# Communication_Display.net
KiCad netlist of a schematic drawn in Altium Designer
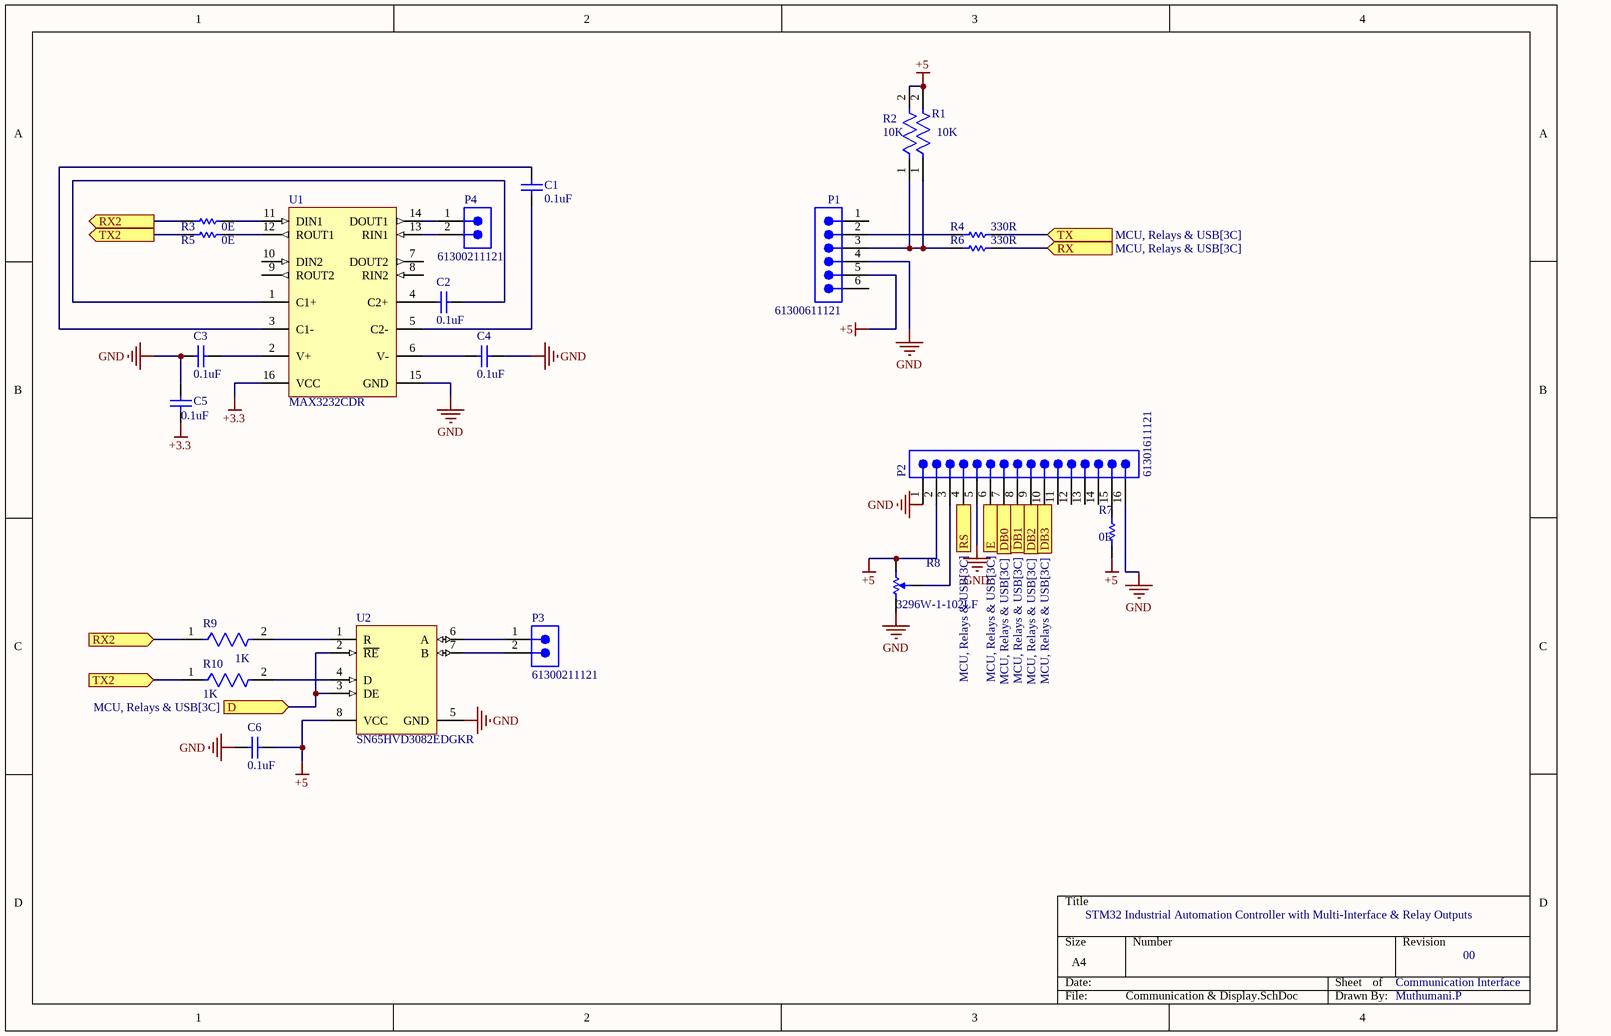
[diagram p0: Communication & Display.SchDoc]

(export (version "E")
  (design (tool "Eeschema 10.0.6"))
  (components
    (comp (ref "C1")
      (value "0.1uF")
      (footprint "CAPC1608X90X35ML10T15")
      (description "Chip Capacitor, 0.1 uF, +/- 10%, 50 V, -55 to 125 degC, 0603 (1608 Metric), RoHS, Tape and Reel")
      (fields (field (name "TOLERANCE") "10%") (field (name "VOLTAGE") "50V"))
      (libsource (lib "Altium Content Vault") (part "CAP-NP-2"))
    )
    (comp (ref "C2")
      (value "0.1uF")
      (footprint "CAPC1608X90X35ML10T15")
      (description "Chip Capacitor, 0.1 uF, +/- 10%, 50 V, -55 to 125 degC, 0603 (1608 Metric), RoHS, Tape and Reel")
      (fields (field (name "TOLERANCE") "10%") (field (name "VOLTAGE") "50V"))
      (libsource (lib "Altium Content Vault") (part "CAP-NP-2"))
    )
    (comp (ref "C3")
      (value "0.1uF")
      (footprint "CAPC1608X90X35ML10T15")
      (description "Chip Capacitor, 0.1 uF, +/- 10%, 50 V, -55 to 125 degC, 0603 (1608 Metric), RoHS, Tape and Reel")
      (fields (field (name "TOLERANCE") "10%") (field (name "VOLTAGE") "50V"))
      (libsource (lib "Altium Content Vault") (part "CAP-NP-2"))
    )
    (comp (ref "C4")
      (value "0.1uF")
      (footprint "CAPC1608X90X35ML10T15")
      (description "Chip Capacitor, 0.1 uF, +/- 10%, 50 V, -55 to 125 degC, 0603 (1608 Metric), RoHS, Tape and Reel")
      (fields (field (name "TOLERANCE") "10%") (field (name "VOLTAGE") "50V"))
      (libsource (lib "Altium Content Vault") (part "CAP-NP-2"))
    )
    (comp (ref "C5")
      (value "0.1uF")
      (footprint "CAPC1608X90X35ML10T15")
      (description "Chip Capacitor, 0.1 uF, +/- 10%, 50 V, -55 to 125 degC, 0603 (1608 Metric), RoHS, Tape and Reel")
      (fields (field (name "TOLERANCE") "10%") (field (name "VOLTAGE") "50V"))
      (libsource (lib "Altium Content Vault") (part "CAP-NP-2"))
    )
    (comp (ref "C6")
      (value "0.1uF")
      (footprint "CAPC1608X90X35ML10T15")
      (description "Chip Capacitor, 0.1 uF, +/- 10%, 50 V, -55 to 125 degC, 0603 (1608 Metric), RoHS, Tape and Reel")
      (fields (field (name "TOLERANCE") "10%") (field (name "VOLTAGE") "50V"))
      (libsource (lib "Altium Content Vault") (part "CAP-NP-2"))
    )
    (comp (ref "P1")
      (value "61300611121")
      (footprint "61300611121")
      (description "THT Vertical Pin Header WR-PHD, Pitch 2.54 mm, Single Row, 6 pins")
      (libsource (lib "Altium Content Vault") (part "Header_Male_1R_06P"))
    )
    (comp (ref "P2")
      (value "61301611121")
      (footprint "61301611121")
      (description "THT Vertical Pin Header WR-PHD, Pitch 2.54 mm, Single Row, 16 pins")
      (libsource (lib "Altium Content Vault") (part "Header_Male_1R_16P"))
    )
    (comp (ref "P3")
      (value "61300211121")
      (footprint "61300211121")
      (description "THT Vertical Pin Header WR-PHD, Pitch 2.54 mm, Single Row, 2 pins")
      (libsource (lib "Altium Content Vault") (part "Header_Male_1R_02P"))
    )
    (comp (ref "P4")
      (value "61300211121")
      (footprint "61300211121")
      (description "THT Vertical Pin Header WR-PHD, Pitch 2.54 mm, Single Row, 2 pins")
      (libsource (lib "Altium Content Vault") (part "Header_Male_1R_02P"))
    )
    (comp (ref "R1")
      (value "10K")
      (footprint "FP-RC0603-0_55-IPC_C")
      (description "RES 10K OHM 1% 1/10W 0603")
      (fields (field (name "TOLERANCE") "1%"))
      (libsource (lib "Altium Content Vault") (part "1029c3af85768c4190bb7ad29bc67b5"))
    )
    (comp (ref "R2")
      (value "10K")
      (footprint "FP-RC0603-0_55-IPC_C")
      (description "RES 10K OHM 1% 1/10W 0603")
      (fields (field (name "TOLERANCE") "1%"))
      (libsource (lib "Altium Content Vault") (part "1029c3af85768c4190bb7ad29bc67b5"))
    )
    (comp (ref "R3")
      (value "0E")
      (footprint "RESC1608X55X25ML10T15")
      (description "Chip Resistor, 0 Ohm, +/- 5%, 0.1 W, -55 to 155 degC, 0603 (1608 Metric), RoHS, Tape and Reel")
      (fields (field (name "TOLERANCE") "5%") (field (name "MANUFACTURER") "Yageo"))
      (libsource (lib "Altium Content Vault") (part "RES-2"))
    )
    (comp (ref "R4")
      (value "330R")
      (footprint "RESC1608X55X25NL10T15")
      (description "Chip Resistor, 330 Ohm, +/- 1%, 0.1 W, -55 to 155 degC, 0603 (1608 Metric), RoHS, Tape and Reel")
      (fields (field (name "TOLERANCE") "10%"))
      (libsource (lib "Altium Content Vault") (part "RES-2"))
    )
    (comp (ref "R5")
      (value "0E")
      (footprint "RESC1608X55X25ML10T15")
      (description "Chip Resistor, 0 Ohm, +/- 5%, 0.1 W, -55 to 155 degC, 0603 (1608 Metric), RoHS, Tape and Reel")
      (fields (field (name "TOLERANCE") "5%") (field (name "MANUFACTURER") "Yageo"))
      (libsource (lib "Altium Content Vault") (part "RES-2"))
    )
    (comp (ref "R6")
      (value "330R")
      (footprint "RESC1608X55X25NL10T15")
      (description "Chip Resistor, 330 Ohm, +/- 1%, 0.1 W, -55 to 155 degC, 0603 (1608 Metric), RoHS, Tape and Reel")
      (fields (field (name "TOLERANCE") "10%"))
      (libsource (lib "Altium Content Vault") (part "RES-2"))
    )
    (comp (ref "R7")
      (value "0E")
      (footprint "RESC1608X55X25ML10T15")
      (description "Chip Resistor, 0 Ohm, +/- 5%, 0.1 W, -55 to 155 degC, 0603 (1608 Metric), RoHS, Tape and Reel")
      (fields (field (name "TOLERANCE") "5%") (field (name "MANUFACTURER") "Yageo"))
      (libsource (lib "Altium Content Vault") (part "RES-2"))
    )
    (comp (ref "R8")
      (value "3296W-1-102LF")
      (footprint "BOUR-3296W-1-3")
      (description "Square Trimpot(R) Trimming Potentiometer, 1000 Ohm, -55 to 125 degC, 3-Pin THD, RoHS, Tube")
      (fields (field (name "TOLERANCE") "1%"))
      (libsource (lib "Altium Content Vault") (part "RES-ADJ-3"))
    )
    (comp (ref "R9")
      (value "1K")
      (footprint "FP-RC0603-0_55-IPC_C")
      (description "RES 1K OHM 1% 1/10W 0603")
      (fields (field (name "TOLERANCE") "1%"))
      (libsource (lib "Altium Content Vault") (part "1029c3af85768c4190bb7ad29bc67b5"))
    )
    (comp (ref "R10")
      (value "1K")
      (footprint "FP-RC0603-0_55-IPC_C")
      (description "RES 1K OHM 1% 1/10W 0603")
      (fields (field (name "TOLERANCE") "1%"))
      (libsource (lib "Altium Content Vault") (part "1029c3af85768c4190bb7ad29bc67b5"))
    )
    (comp (ref "U1")
      (value "MAX3232CDR")
      (footprint "D0016A_L")
      (libsource (lib "Altium Content Vault") (part "TI-MAX3232-SOIC_D-16"))
    )
    (comp (ref "U2")
      (value "SN65HVD3082EDGKR")
      (footprint "DGK0008A_M")
      (fields (field (name "MANUFACTURER") "Texas Instruments"))
      (libsource (lib "Altium Content Vault") (part "TI-SN65HVD3082E-MSOP_DGK-8"))
    )
  )
  (nets
    (net (code "1") (name "+3.3") (class "Default")
      (node (ref "C5") (pin "2") (pinfunction "2_2") (pintype "passive"))
      (node (ref "U1") (pin "16") (pinfunction "VCC_16") (pintype "power_in"))
    )
    (net (code "2") (name "+5") (class "Default")
      (node (ref "C6") (pin "1") (pinfunction "1_1") (pintype "passive"))
      (node (ref "P1") (pin "5") (pinfunction "5_5") (pintype "passive"))
      (node (ref "P2") (pin "2") (pinfunction "2_2") (pintype "passive"))
      (node (ref "R1") (pin "2") (pinfunction "2_2") (pintype "passive"))
      (node (ref "R2") (pin "2") (pinfunction "2_2") (pintype "passive"))
      (node (ref "R7") (pin "1") (pinfunction "1_1") (pintype "passive"))
      (node (ref "R8") (pin "2") (pinfunction "B_2") (pintype "passive"))
      (node (ref "U2") (pin "8") (pinfunction "VCC_8") (pintype "power_in"))
    )
    (net (code "3") (name "/D") (class "Default")
      (node (ref "U2") (pin "2") (pinfunction "~{RE}_2") (pintype "input"))
      (node (ref "U2") (pin "3") (pinfunction "DE_3") (pintype "input"))
    )
    (net (code "4") (name "/DB0") (class "Default")
      (node (ref "P2") (pin "7") (pinfunction "7_7") (pintype "passive"))
    )
    (net (code "5") (name "/DB1") (class "Default")
      (node (ref "P2") (pin "8") (pinfunction "8_8") (pintype "passive"))
    )
    (net (code "6") (name "/DB2") (class "Default")
      (node (ref "P2") (pin "9") (pinfunction "9_9") (pintype "passive"))
    )
    (net (code "7") (name "/DB3") (class "Default")
      (node (ref "P2") (pin "10") (pinfunction "10_10") (pintype "passive"))
    )
    (net (code "8") (name "/E") (class "Default")
      (node (ref "P2") (pin "6") (pinfunction "6_6") (pintype "passive"))
    )
    (net (code "9") (name "/RS") (class "Default")
      (node (ref "P2") (pin "4") (pinfunction "4_4") (pintype "passive"))
    )
    (net (code "10") (name "/RX") (class "Default")
      (node (ref "R6") (pin "2") (pinfunction "2_2") (pintype "passive"))
    )
    (net (code "11") (name "/RX2") (class "Default")
      (node (ref "R3") (pin "1") (pinfunction "1_1") (pintype "passive"))
      (node (ref "R9") (pin "1") (pinfunction "1_1") (pintype "passive"))
    )
    (net (code "12") (name "/TX") (class "Default")
      (node (ref "R4") (pin "2") (pinfunction "2_2") (pintype "passive"))
    )
    (net (code "13") (name "/TX2") (class "Default")
      (node (ref "R10") (pin "1") (pinfunction "1_1") (pintype "passive"))
      (node (ref "R5") (pin "1") (pinfunction "1_1") (pintype "passive"))
    )
    (net (code "14") (name "GND") (class "Default")
      (node (ref "C3") (pin "2") (pinfunction "2_2") (pintype "passive"))
      (node (ref "C4") (pin "2") (pinfunction "2_2") (pintype "passive"))
      (node (ref "C5") (pin "1") (pinfunction "1_1") (pintype "passive"))
      (node (ref "C6") (pin "2") (pinfunction "2_2") (pintype "passive"))
      (node (ref "P1") (pin "4") (pinfunction "4_4") (pintype "passive"))
      (node (ref "P2") (pin "1") (pinfunction "1_1") (pintype "passive"))
      (node (ref "P2") (pin "16") (pinfunction "16_16") (pintype "passive"))
      (node (ref "P2") (pin "5") (pinfunction "5_5") (pintype "passive"))
      (node (ref "R8") (pin "1") (pinfunction "A_1") (pintype "passive"))
      (node (ref "U1") (pin "15") (pinfunction "GND_15") (pintype "power_in"))
      (node (ref "U2") (pin "5") (pinfunction "GND_5") (pintype "power_in"))
    )
    (net (code "15") (name "Net-(P1-Pad2)") (class "Default")
      (node (ref "P1") (pin "2") (pinfunction "2_2") (pintype "passive"))
      (node (ref "R4") (pin "1") (pinfunction "1_1") (pintype "passive"))
    )
    (net (code "16") (name "Net-(P1-Pad3)") (class "Default")
      (node (ref "P1") (pin "3") (pinfunction "3_3") (pintype "passive"))
      (node (ref "R1") (pin "1") (pinfunction "1_1") (pintype "passive"))
      (node (ref "R2") (pin "1") (pinfunction "1_1") (pintype "passive"))
      (node (ref "R6") (pin "1") (pinfunction "1_1") (pintype "passive"))
    )
    (net (code "17") (name "Net-(P2-Pad15)") (class "Default")
      (node (ref "P2") (pin "15") (pinfunction "15_15") (pintype "passive"))
      (node (ref "R7") (pin "2") (pinfunction "2_2") (pintype "passive"))
    )
    (net (code "18") (name "Net-(R8-TAP)") (class "Default")
      (node (ref "P2") (pin "3") (pinfunction "3_3") (pintype "passive"))
      (node (ref "R8") (pin "3") (pinfunction "TAP_3") (pintype "passive"))
    )
    (net (code "19") (name "Net-(U1-C1+)") (class "Default")
      (node (ref "C2") (pin "2") (pinfunction "2_2") (pintype "passive"))
      (node (ref "U1") (pin "1") (pinfunction "C1+_1") (pintype "passive"))
    )
    (net (code "20") (name "Net-(U1-C1-)") (class "Default")
      (node (ref "C1") (pin "2") (pinfunction "2_2") (pintype "passive"))
      (node (ref "U1") (pin "3") (pinfunction "C1-_3") (pintype "passive"))
    )
    (net (code "21") (name "Net-(U1-C2+)") (class "Default")
      (node (ref "C2") (pin "1") (pinfunction "1_1") (pintype "passive"))
      (node (ref "U1") (pin "4") (pinfunction "C2+_4") (pintype "passive"))
    )
    (net (code "22") (name "Net-(U1-C2-)") (class "Default")
      (node (ref "C1") (pin "1") (pinfunction "1_1") (pintype "passive"))
      (node (ref "U1") (pin "5") (pinfunction "C2-_5") (pintype "passive"))
    )
    (net (code "23") (name "Net-(U1-DIN1)") (class "Default")
      (node (ref "R3") (pin "2") (pinfunction "2_2") (pintype "passive"))
      (node (ref "U1") (pin "11") (pinfunction "DIN1_11") (pintype "input"))
    )
    (net (code "24") (name "Net-(U1-DOUT1)") (class "Default")
      (node (ref "P4") (pin "1") (pinfunction "1_1") (pintype "passive"))
      (node (ref "U1") (pin "14") (pinfunction "DOUT1_14") (pintype "output"))
    )
    (net (code "25") (name "Net-(U1-RIN1)") (class "Default")
      (node (ref "P4") (pin "2") (pinfunction "2_2") (pintype "passive"))
      (node (ref "U1") (pin "13") (pinfunction "RIN1_13") (pintype "input"))
    )
    (net (code "26") (name "Net-(U1-ROUT1)") (class "Default")
      (node (ref "R5") (pin "2") (pinfunction "2_2") (pintype "passive"))
      (node (ref "U1") (pin "12") (pinfunction "ROUT1_12") (pintype "output"))
    )
    (net (code "27") (name "Net-(U1-V+)") (class "Default")
      (node (ref "C3") (pin "1") (pinfunction "1_1") (pintype "passive"))
      (node (ref "U1") (pin "2") (pinfunction "V+_2") (pintype "power_in"))
    )
    (net (code "28") (name "Net-(U1-V-)") (class "Default")
      (node (ref "C4") (pin "1") (pinfunction "1_1") (pintype "passive"))
      (node (ref "U1") (pin "6") (pinfunction "V-_6") (pintype "power_in"))
    )
    (net (code "29") (name "Net-(U2-A)") (class "Default")
      (node (ref "P3") (pin "1") (pinfunction "1_1") (pintype "passive"))
      (node (ref "U2") (pin "6") (pinfunction "A_6") (pintype "bidirectional"))
    )
    (net (code "30") (name "Net-(U2-B)") (class "Default")
      (node (ref "P3") (pin "2") (pinfunction "2_2") (pintype "passive"))
      (node (ref "U2") (pin "7") (pinfunction "B_7") (pintype "bidirectional"))
    )
    (net (code "31") (name "Net-(U2-D)") (class "Default")
      (node (ref "R10") (pin "2") (pinfunction "2_2") (pintype "passive"))
      (node (ref "U2") (pin "4") (pinfunction "D_4") (pintype "input"))
    )
    (net (code "32") (name "Net-(U2-R)") (class "Default")
      (node (ref "R9") (pin "2") (pinfunction "2_2") (pintype "passive"))
      (node (ref "U2") (pin "1") (pinfunction "R_1") (pintype "tri_state"))
    )
    (net (code "33") (name "unconnected-(P1-Pad1)") (class "Default")
      (node (ref "P1") (pin "1") (pinfunction "1_1") (pintype "passive"))
    )
    (net (code "34") (name "unconnected-(P1-Pad6)") (class "Default")
      (node (ref "P1") (pin "6") (pinfunction "6_6") (pintype "passive"))
    )
    (net (code "35") (name "unconnected-(P2-Pad11)") (class "Default")
      (node (ref "P2") (pin "11") (pinfunction "11_11") (pintype "passive"))
    )
    (net (code "36") (name "unconnected-(P2-Pad12)") (class "Default")
      (node (ref "P2") (pin "12") (pinfunction "12_12") (pintype "passive"))
    )
    (net (code "37") (name "unconnected-(P2-Pad13)") (class "Default")
      (node (ref "P2") (pin "13") (pinfunction "13_13") (pintype "passive"))
    )
    (net (code "38") (name "unconnected-(P2-Pad14)") (class "Default")
      (node (ref "P2") (pin "14") (pinfunction "14_14") (pintype "passive"))
    )
    (net (code "39") (name "unconnected-(U1-DIN2-Pad10)") (class "Default")
      (node (ref "U1") (pin "10") (pinfunction "DIN2_10") (pintype "input"))
    )
    (net (code "40") (name "unconnected-(U1-DOUT2-Pad7)") (class "Default")
      (node (ref "U1") (pin "7") (pinfunction "DOUT2_7") (pintype "output"))
    )
    (net (code "41") (name "unconnected-(U1-RIN2-Pad8)") (class "Default")
      (node (ref "U1") (pin "8") (pinfunction "RIN2_8") (pintype "input"))
    )
    (net (code "42") (name "unconnected-(U1-ROUT2-Pad9)") (class "Default")
      (node (ref "U1") (pin "9") (pinfunction "ROUT2_9") (pintype "output"))
    )
  )
)
